# Launch_Tower_Power_System_Board_v1-1.net
KiCad netlist of a schematic drawn in EAGLE
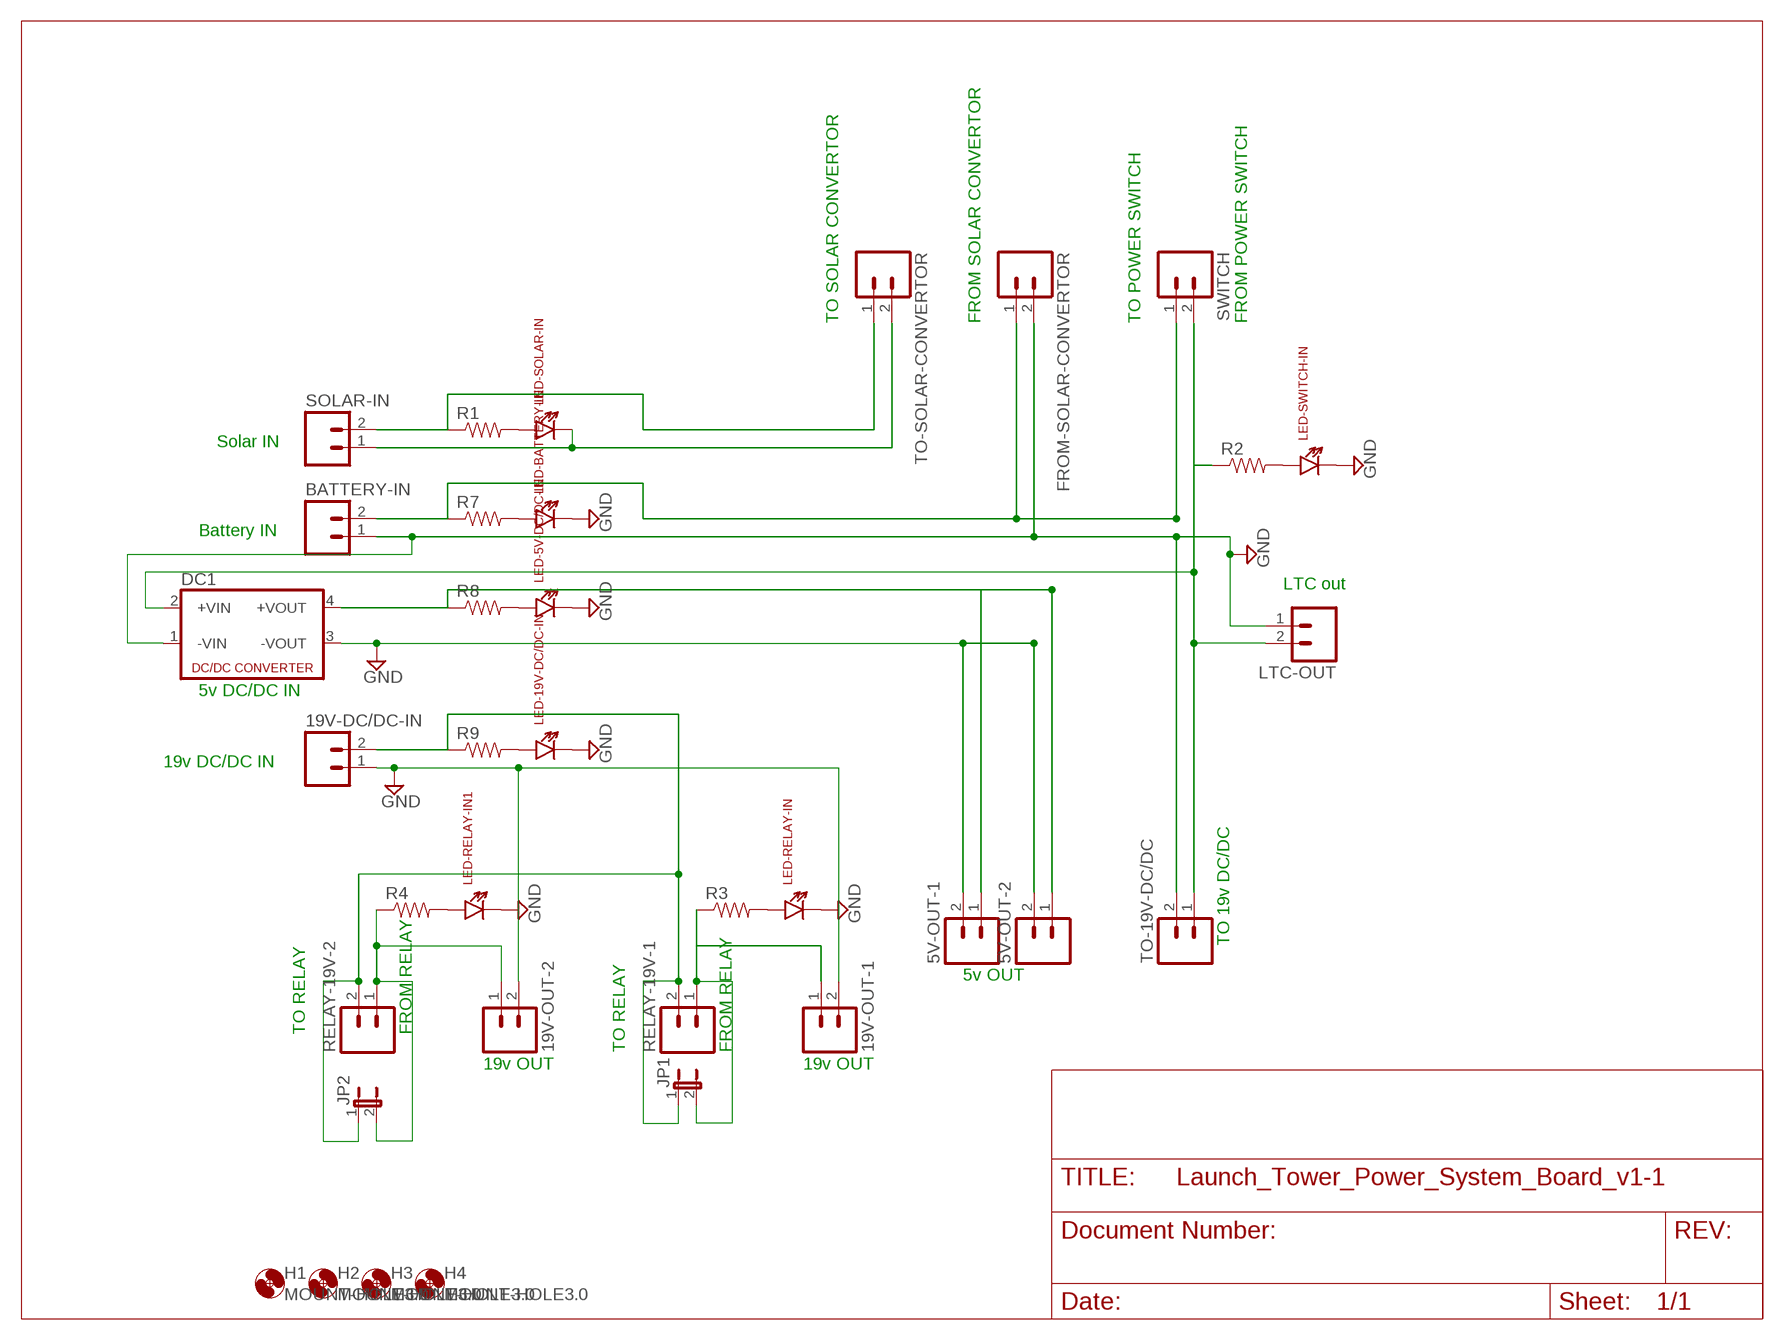
[diagram p0: schematic, sheet 1]

(export (version "E")
  (design (tool "Eeschema 10.0.6"))
  (components
    (comp (ref "5V-OUT-1")
      (value "M023.5MM")
      (footprint "eagle-import:SCREWTERMINAL-3.5MM-2")
      (libsource (lib "eagle-import") (part "M023.5MM"))
    )
    (comp (ref "5V-OUT-2")
      (value "M023.5MM")
      (footprint "eagle-import:SCREWTERMINAL-3.5MM-2")
      (libsource (lib "eagle-import") (part "M023.5MM"))
    )
    (comp (ref "19V-DC/DC-IN")
      (value "M025MM")
      (footprint "eagle-import:SCREWTERMINAL-5MM-2")
      (libsource (lib "eagle-import") (part "M025MM"))
    )
    (comp (ref "19V-OUT-1")
      (value "M025MM")
      (footprint "eagle-import:SCREWTERMINAL-5MM-2")
      (libsource (lib "eagle-import") (part "M025MM"))
    )
    (comp (ref "19V-OUT-2")
      (value "M025MM")
      (footprint "eagle-import:SCREWTERMINAL-5MM-2")
      (libsource (lib "eagle-import") (part "M025MM"))
    )
    (comp (ref "BATTERY-IN")
      (value "M025MM")
      (footprint "eagle-import:SCREWTERMINAL-5MM-2")
      (libsource (lib "eagle-import") (part "M025MM"))
    )
    (comp (ref "DC1")
      (value "NME")
      (footprint "eagle-import:NME")
      (fields (field (name "MF") "C & D TECHNOLOGIES, INC") (field (name "MPN") "NME1205D"))
      (libsource (lib "eagle-import") (part "NME"))
    )
    (comp (ref "FROM-SOLAR-CONVERTOR")
      (value "M025MM")
      (footprint "eagle-import:SCREWTERMINAL-5MM-2")
      (libsource (lib "eagle-import") (part "M025MM"))
    )
    (comp (ref "H1")
      (value "MOUNT-HOLE3.0")
      (footprint "eagle-import:3,0")
      (libsource (lib "eagle-import") (part "MOUNT-HOLE3.0"))
    )
    (comp (ref "H2")
      (value "MOUNT-HOLE3.0")
      (footprint "eagle-import:3,0")
      (libsource (lib "eagle-import") (part "MOUNT-HOLE3.0"))
    )
    (comp (ref "H3")
      (value "MOUNT-HOLE3.0")
      (footprint "eagle-import:3,0")
      (libsource (lib "eagle-import") (part "MOUNT-HOLE3.0"))
    )
    (comp (ref "H4")
      (value "MOUNT-HOLE3.0")
      (footprint "eagle-import:3,0")
      (libsource (lib "eagle-import") (part "MOUNT-HOLE3.0"))
    )
    (comp (ref "JP1")
      (value "JUMPER-2PTH")
      (footprint "eagle-import:1X02")
      (libsource (lib "eagle-import") (part "JUMPER-2PTH"))
    )
    (comp (ref "JP2")
      (value "JUMPER-2PTH")
      (footprint "eagle-import:1X02")
      (libsource (lib "eagle-import") (part "JUMPER-2PTH"))
    )
    (comp (ref "LED-5V-DC/DC-IN")
      (value "LTE-302")
      (footprint "eagle-import:LTE-302")
      (libsource (lib "eagle-import") (part "LTE-302"))
    )
    (comp (ref "LED-19V-DC/DC-IN")
      (value "LTE-302")
      (footprint "eagle-import:LTE-302")
      (libsource (lib "eagle-import") (part "LTE-302"))
    )
    (comp (ref "LED-BATTERY-IN")
      (value "LTE-302")
      (footprint "eagle-import:LTE-302")
      (libsource (lib "eagle-import") (part "LTE-302"))
    )
    (comp (ref "LED-RELAY-IN")
      (value "LTE-302")
      (footprint "eagle-import:LTE-302")
      (libsource (lib "eagle-import") (part "LTE-302"))
    )
    (comp (ref "LED-RELAY-IN1")
      (value "LTE-302")
      (footprint "eagle-import:LTE-302")
      (libsource (lib "eagle-import") (part "LTE-302"))
    )
    (comp (ref "LED-SOLAR-IN")
      (value "LTE-302")
      (footprint "eagle-import:LTE-302")
      (libsource (lib "eagle-import") (part "LTE-302"))
    )
    (comp (ref "LED-SWITCH-IN")
      (value "LTE-302")
      (footprint "eagle-import:LTE-302")
      (libsource (lib "eagle-import") (part "LTE-302"))
    )
    (comp (ref "LTC-OUT")
      (value "M025MM")
      (footprint "eagle-import:SCREWTERMINAL-5MM-2")
      (libsource (lib "eagle-import") (part "M025MM"))
    )
    (comp (ref "R1")
      (value "RESISTORPTH-1/2W")
      (footprint "eagle-import:AXIAL-0.5")
      (libsource (lib "eagle-import") (part "RESISTORPTH-1/2W"))
    )
    (comp (ref "R2")
      (value "RESISTORPTH-1/2W")
      (footprint "eagle-import:AXIAL-0.5")
      (libsource (lib "eagle-import") (part "RESISTORPTH-1/2W"))
    )
    (comp (ref "R3")
      (value "RESISTORPTH-1/2W")
      (footprint "eagle-import:AXIAL-0.5")
      (libsource (lib "eagle-import") (part "RESISTORPTH-1/2W"))
    )
    (comp (ref "R4")
      (value "RESISTORPTH-1/2W")
      (footprint "eagle-import:AXIAL-0.5")
      (libsource (lib "eagle-import") (part "RESISTORPTH-1/2W"))
    )
    (comp (ref "R7")
      (value "RESISTORPTH-1/2W")
      (footprint "eagle-import:AXIAL-0.5")
      (libsource (lib "eagle-import") (part "RESISTORPTH-1/2W"))
    )
    (comp (ref "R8")
      (value "RESISTORPTH-1/2W")
      (footprint "eagle-import:AXIAL-0.5")
      (libsource (lib "eagle-import") (part "RESISTORPTH-1/2W"))
    )
    (comp (ref "R9")
      (value "RESISTORPTH-1/2W")
      (footprint "eagle-import:AXIAL-0.5")
      (libsource (lib "eagle-import") (part "RESISTORPTH-1/2W"))
    )
    (comp (ref "RELAY-19V-1")
      (value "M025MM")
      (footprint "eagle-import:SCREWTERMINAL-5MM-2")
      (libsource (lib "eagle-import") (part "M025MM"))
    )
    (comp (ref "RELAY-19V-2")
      (value "M025MM")
      (footprint "eagle-import:SCREWTERMINAL-5MM-2")
      (libsource (lib "eagle-import") (part "M025MM"))
    )
    (comp (ref "SOLAR-IN")
      (value "M025MM")
      (footprint "eagle-import:SCREWTERMINAL-5MM-2")
      (libsource (lib "eagle-import") (part "M025MM"))
    )
    (comp (ref "SWITCH")
      (value "M025MM")
      (footprint "eagle-import:SCREWTERMINAL-5MM-2")
      (libsource (lib "eagle-import") (part "M025MM"))
    )
    (comp (ref "TO-19V-DC/DC")
      (value "M025MM")
      (footprint "eagle-import:SCREWTERMINAL-5MM-2")
      (libsource (lib "eagle-import") (part "M025MM"))
    )
    (comp (ref "TO-SOLAR-CONVERTOR")
      (value "M025MM")
      (footprint "eagle-import:SCREWTERMINAL-5MM-2")
      (libsource (lib "eagle-import") (part "M025MM"))
    )
  )
  (nets
    (net (code "1") (name "GND") (class "Default")
      (node (ref "19V-DC/DC-IN") (pin "1") (pinfunction "1_1") (pintype "passive"))
      (node (ref "19V-OUT-1") (pin "2") (pinfunction "2_2") (pintype "passive"))
      (node (ref "19V-OUT-2") (pin "2") (pinfunction "2_2") (pintype "passive"))
      (node (ref "5V-OUT-1") (pin "2") (pinfunction "2_2") (pintype "passive"))
      (node (ref "5V-OUT-2") (pin "2") (pinfunction "2_2") (pintype "passive"))
      (node (ref "BATTERY-IN") (pin "1") (pinfunction "1_1") (pintype "passive"))
      (node (ref "DC1") (pin "1") (pinfunction "-VIN_1") (pintype "passive"))
      (node (ref "DC1") (pin "3") (pinfunction "-VOUT_3") (pintype "passive"))
      (node (ref "FROM-SOLAR-CONVERTOR") (pin "2") (pinfunction "2_2") (pintype "passive"))
      (node (ref "LED-19V-DC/DC-IN") (pin "C") (pinfunction "C_C") (pintype "bidirectional"))
      (node (ref "LED-5V-DC/DC-IN") (pin "C") (pinfunction "C_C") (pintype "bidirectional"))
      (node (ref "LED-BATTERY-IN") (pin "C") (pinfunction "C_C") (pintype "bidirectional"))
      (node (ref "LED-RELAY-IN") (pin "C") (pinfunction "C_C") (pintype "bidirectional"))
      (node (ref "LED-RELAY-IN1") (pin "C") (pinfunction "C_C") (pintype "bidirectional"))
      (node (ref "LED-SWITCH-IN") (pin "C") (pinfunction "C_C") (pintype "bidirectional"))
      (node (ref "LTC-OUT") (pin "1") (pinfunction "1_1") (pintype "passive"))
      (node (ref "TO-19V-DC/DC") (pin "2") (pinfunction "2_2") (pintype "passive"))
    )
    (net (code "2") (name "Net-(DC1-+VIN)") (class "Default")
      (node (ref "DC1") (pin "2") (pinfunction "+VIN_2") (pintype "passive"))
      (node (ref "LTC-OUT") (pin "2") (pinfunction "2_2") (pintype "passive"))
      (node (ref "R2") (pin "P$1") (pinfunction "1_P$1") (pintype "passive"))
      (node (ref "SWITCH") (pin "2") (pinfunction "2_2") (pintype "passive"))
      (node (ref "TO-19V-DC/DC") (pin "1") (pinfunction "1_1") (pintype "passive"))
    )
    (net (code "3") (name "Net-(DC1-+VOUT)") (class "Default")
      (node (ref "5V-OUT-1") (pin "1") (pinfunction "1_1") (pintype "passive"))
      (node (ref "5V-OUT-2") (pin "1") (pinfunction "1_1") (pintype "passive"))
      (node (ref "DC1") (pin "4") (pinfunction "+VOUT_4") (pintype "passive"))
      (node (ref "R8") (pin "P$1") (pinfunction "1_P$1") (pintype "passive"))
    )
    (net (code "4") (name "Net-(LED-SOLAR-IN-PadC)") (class "Default")
      (node (ref "LED-SOLAR-IN") (pin "C") (pinfunction "C_C") (pintype "bidirectional"))
      (node (ref "SOLAR-IN") (pin "1") (pinfunction "1_1") (pintype "passive"))
      (node (ref "TO-SOLAR-CONVERTOR") (pin "2") (pinfunction "2_2") (pintype "passive"))
    )
    (net (code "5") (name "Net-(R1-1)") (class "Default")
      (node (ref "R1") (pin "P$1") (pinfunction "1_P$1") (pintype "passive"))
      (node (ref "SOLAR-IN") (pin "2") (pinfunction "2_2") (pintype "passive"))
      (node (ref "TO-SOLAR-CONVERTOR") (pin "1") (pinfunction "1_1") (pintype "passive"))
    )
    (net (code "6") (name "Net-(R1-2)") (class "Default")
      (node (ref "LED-SOLAR-IN") (pin "A") (pinfunction "A_A") (pintype "bidirectional"))
      (node (ref "R1") (pin "P$2") (pinfunction "2_P$2") (pintype "passive"))
    )
    (net (code "7") (name "Net-(R2-2)") (class "Default")
      (node (ref "LED-SWITCH-IN") (pin "A") (pinfunction "A_A") (pintype "bidirectional"))
      (node (ref "R2") (pin "P$2") (pinfunction "2_P$2") (pintype "passive"))
    )
    (net (code "8") (name "Net-(R3-1)") (class "Default")
      (node (ref "19V-OUT-1") (pin "1") (pinfunction "1_1") (pintype "passive"))
      (node (ref "JP1") (pin "2") (pinfunction "2_2") (pintype "passive"))
      (node (ref "R3") (pin "P$1") (pinfunction "1_P$1") (pintype "passive"))
      (node (ref "RELAY-19V-1") (pin "1") (pinfunction "1_1") (pintype "passive"))
    )
    (net (code "9") (name "Net-(R3-2)") (class "Default")
      (node (ref "LED-RELAY-IN") (pin "A") (pinfunction "A_A") (pintype "bidirectional"))
      (node (ref "R3") (pin "P$2") (pinfunction "2_P$2") (pintype "passive"))
    )
    (net (code "10") (name "Net-(R4-1)") (class "Default")
      (node (ref "19V-OUT-2") (pin "1") (pinfunction "1_1") (pintype "passive"))
      (node (ref "JP2") (pin "2") (pinfunction "2_2") (pintype "passive"))
      (node (ref "R4") (pin "P$1") (pinfunction "1_P$1") (pintype "passive"))
      (node (ref "RELAY-19V-2") (pin "1") (pinfunction "1_1") (pintype "passive"))
    )
    (net (code "11") (name "Net-(R4-2)") (class "Default")
      (node (ref "LED-RELAY-IN1") (pin "A") (pinfunction "A_A") (pintype "bidirectional"))
      (node (ref "R4") (pin "P$2") (pinfunction "2_P$2") (pintype "passive"))
    )
    (net (code "12") (name "Net-(R7-1)") (class "Default")
      (node (ref "BATTERY-IN") (pin "2") (pinfunction "2_2") (pintype "passive"))
      (node (ref "FROM-SOLAR-CONVERTOR") (pin "1") (pinfunction "1_1") (pintype "passive"))
      (node (ref "R7") (pin "P$1") (pinfunction "1_P$1") (pintype "passive"))
      (node (ref "SWITCH") (pin "1") (pinfunction "1_1") (pintype "passive"))
    )
    (net (code "13") (name "Net-(R7-2)") (class "Default")
      (node (ref "LED-BATTERY-IN") (pin "A") (pinfunction "A_A") (pintype "bidirectional"))
      (node (ref "R7") (pin "P$2") (pinfunction "2_P$2") (pintype "passive"))
    )
    (net (code "14") (name "Net-(R8-2)") (class "Default")
      (node (ref "LED-5V-DC/DC-IN") (pin "A") (pinfunction "A_A") (pintype "bidirectional"))
      (node (ref "R8") (pin "P$2") (pinfunction "2_P$2") (pintype "passive"))
    )
    (net (code "15") (name "Net-(R9-1)") (class "Default")
      (node (ref "19V-DC/DC-IN") (pin "2") (pinfunction "2_2") (pintype "passive"))
      (node (ref "JP1") (pin "1") (pinfunction "1_1") (pintype "passive"))
      (node (ref "JP2") (pin "1") (pinfunction "1_1") (pintype "passive"))
      (node (ref "R9") (pin "P$1") (pinfunction "1_P$1") (pintype "passive"))
      (node (ref "RELAY-19V-1") (pin "2") (pinfunction "2_2") (pintype "passive"))
      (node (ref "RELAY-19V-2") (pin "2") (pinfunction "2_2") (pintype "passive"))
    )
    (net (code "16") (name "Net-(R9-2)") (class "Default")
      (node (ref "LED-19V-DC/DC-IN") (pin "A") (pinfunction "A_A") (pintype "bidirectional"))
      (node (ref "R9") (pin "P$2") (pinfunction "2_P$2") (pintype "passive"))
    )
  )
)
